# ir-board.net
KiCad netlist of a schematic drawn in EAGLE
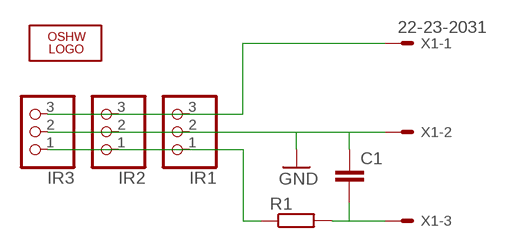
[diagram p0: schematic, sheet 1]

(export (version "E")
  (design (tool "Eeschema 10.0.6"))
  (components
    (comp (ref "C1")
      (value "C-EUC1206")
      (footprint "eagle-import:C1206")
      (libsource (lib "eagle-import") (part "C-EUC1206"))
    )
    (comp (ref "IR1")
      (value "PINHD-1X3")
      (footprint "eagle-import:1X03")
      (libsource (lib "eagle-import") (part "PINHD-1X3"))
    )
    (comp (ref "IR2")
      (value "PINHD-1X3")
      (footprint "eagle-import:1X03")
      (libsource (lib "eagle-import") (part "PINHD-1X3"))
    )
    (comp (ref "IR3")
      (value "PINHD-1X3")
      (footprint "eagle-import:1X03")
      (libsource (lib "eagle-import") (part "PINHD-1X3"))
    )
    (comp (ref "LOGO1")
      (value "OSHW_LOGO_6MILX0200-NT")
      (footprint "eagle-import:OSHW_6X200_NOTEXT")
      (libsource (lib "eagle-import") (part "OSHW_LOGO_6MILX0200-NT"))
    )
    (comp (ref "R1")
      (value "R-EU_R1206")
      (footprint "eagle-import:R1206")
      (libsource (lib "eagle-import") (part "R-EU_R1206"))
    )
    (comp (ref "X1")
      (value "22-23-2031")
      (footprint "eagle-import:22-23-2031")
      (fields (field (name "MF") "MOLEX"))
      (libsource (lib "eagle-import") (part "22-23-2031"))
    )
  )
  (nets
    (net (code "1") (name "GND") (class "Default")
      (node (ref "C1") (pin "1") (pinfunction "1_1") (pintype "passive"))
      (node (ref "IR1") (pin "2") (pinfunction "2_2") (pintype "passive"))
      (node (ref "IR2") (pin "2") (pinfunction "2_2") (pintype "passive"))
      (node (ref "IR3") (pin "2") (pinfunction "2_2") (pintype "passive"))
      (node (ref "X1") (pin "2") (pinfunction "S_2") (pintype "passive"))
    )
    (net (code "2") (name "Net-(IR1-Pad1)") (class "Default")
      (node (ref "IR1") (pin "1") (pinfunction "1_1") (pintype "passive"))
      (node (ref "IR2") (pin "1") (pinfunction "1_1") (pintype "passive"))
      (node (ref "IR3") (pin "1") (pinfunction "1_1") (pintype "passive"))
      (node (ref "R1") (pin "1") (pinfunction "1_1") (pintype "passive"))
    )
    (net (code "3") (name "Net-(X1A-S)") (class "Default")
      (node (ref "IR1") (pin "3") (pinfunction "3_3") (pintype "passive"))
      (node (ref "IR2") (pin "3") (pinfunction "3_3") (pintype "passive"))
      (node (ref "IR3") (pin "3") (pinfunction "3_3") (pintype "passive"))
      (node (ref "X1") (pin "1") (pinfunction "S_1") (pintype "passive"))
    )
    (net (code "4") (name "Net-(X1C-S)") (class "Default")
      (node (ref "C1") (pin "2") (pinfunction "2_2") (pintype "passive"))
      (node (ref "R1") (pin "2") (pinfunction "2_2") (pintype "passive"))
      (node (ref "X1") (pin "3") (pinfunction "S_3") (pintype "passive"))
    )
  )
)
